# care.net
KiCad netlist of a schematic drawn in Altium Designer
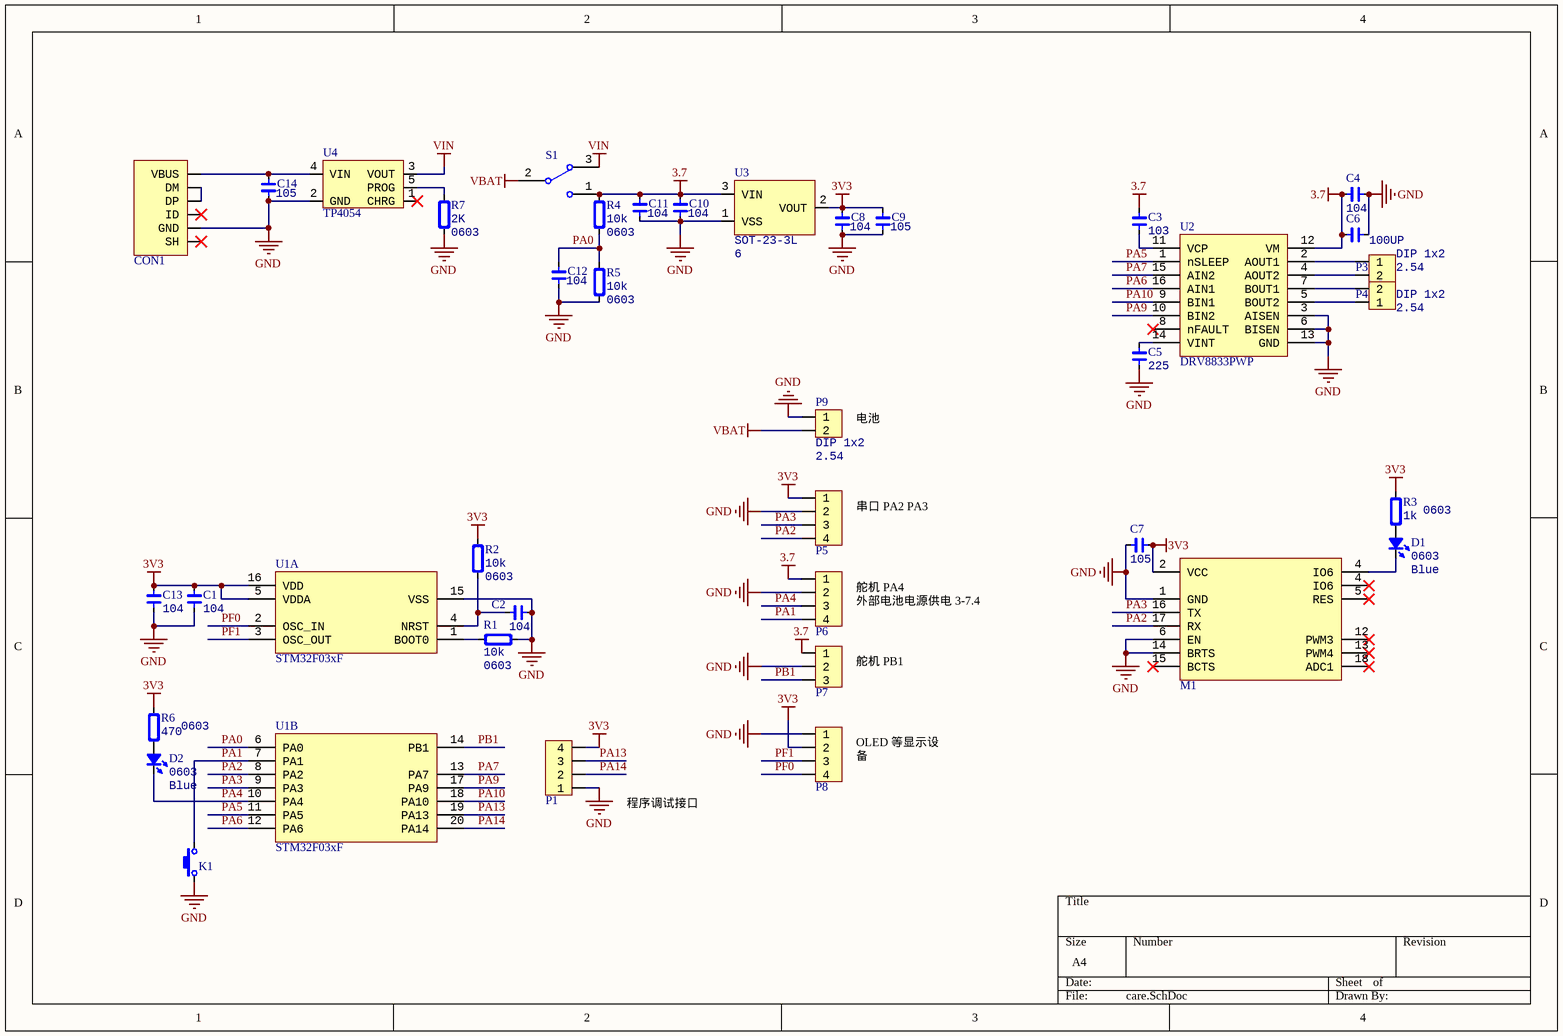
[diagram p0: care.SchDoc]

(export (version "E")
  (design (tool "Eeschema 10.0.6"))
  (components
    (comp (ref "C1")
      (value "104")
      (footprint "PCB_PassiveCap:CAP_0603")
      (description "Capacitor")
      (libsource (lib "") (part "Cap_0603_2"))
    )
    (comp (ref "C2")
      (value "104")
      (footprint "PCB_PassiveCap:CAP_0603")
      (description "Capacitor")
      (libsource (lib "SCH_Passive") (part "Cap_0603"))
    )
    (comp (ref "C3")
      (value "103")
      (footprint "PCB_PassiveCap:CAP_0603")
      (description "Capacitor")
      (libsource (lib "") (part "Cap_0603_2"))
    )
    (comp (ref "C4")
      (value "104")
      (footprint "PCB_PassiveCap:CAP_0603")
      (description "Capacitor")
      (libsource (lib "SCH_Passive") (part "Cap_0603"))
    )
    (comp (ref "C5")
      (value "225")
      (footprint "PCB_PassiveCap:CAP_0603")
      (description "Capacitor")
      (libsource (lib "") (part "Cap_0603_2"))
    )
    (comp (ref "C6")
      (value "100UP")
      (footprint "PCB_PassiveCap:CAP_TAN_B1210")
      (description "Capacitor")
      (libsource (lib "SCH_Passive") (part "Cap_0603"))
    )
    (comp (ref "C7")
      (value "105")
      (footprint "PCB_PassiveCap:CAP_0603")
      (description "Capacitor")
      (libsource (lib "") (part "Cap_0603_3"))
    )
    (comp (ref "C8")
      (value "104")
      (footprint "PCB_PassiveCap:CAP_0603")
      (description "Capacitor")
      (libsource (lib "") (part "Cap_0603_1"))
    )
    (comp (ref "C9")
      (value "105")
      (footprint "PCB_PassiveCap:CAP_0603")
      (description "Capacitor")
      (libsource (lib "") (part "Cap_0603_1"))
    )
    (comp (ref "C10")
      (value "104")
      (footprint "PCB_PassiveCap:CAP_0603")
      (description "Capacitor")
      (libsource (lib "") (part "Cap_0603_1"))
    )
    (comp (ref "C11")
      (value "104")
      (footprint "PCB_PassiveCap:CAP_0603")
      (description "Capacitor")
      (libsource (lib "") (part "Cap_0603_1"))
    )
    (comp (ref "C12")
      (value "104")
      (footprint "PCB_PassiveCap:CAP_0603")
      (description "Capacitor")
      (libsource (lib "") (part "Cap_0603_1"))
    )
    (comp (ref "C13")
      (value "104")
      (footprint "PCB_PassiveCap:CAP_0603")
      (description "Capacitor")
      (libsource (lib "") (part "Cap_0603_2"))
    )
    (comp (ref "C14")
      (value "105")
      (footprint "PCB_PassiveCap:CAP_0603")
      (description "Capacitor")
      (libsource (lib "") (part "Cap_0603_1"))
    )
    (comp (ref "CON1")
      (value "MicroUSB")
      (footprint "PCB_USB:USB_Micro-AB")
      (description "USB")
      (libsource (lib "SCH_USB") (part "USB_Micro"))
    )
    (comp (ref "D1")
      (value "Blue")
      (footprint "PCB_ActiveLED:LED_0603_RED")
      (description "LED")
      (fields (field (name "TYPE") "0603"))
      (libsource (lib "SCH_Active") (part "LED_0603"))
    )
    (comp (ref "D2")
      (value "Blue")
      (footprint "PCB_ActiveLED:LED_0603_RED")
      (description "LED")
      (fields (field (name "TYPE") "0603"))
      (libsource (lib "SCH_Active") (part "LED_0603"))
    )
    (comp (ref "K1")
      (value "ButtonTACT")
      (footprint "PCB_Switch:ButtonTACT_3x4x2_180H")
      (description "Button")
      (libsource (lib "SCH_Switch") (part "ButtonTACT_3x4x2_180"))
    )
    (comp (ref "M1")
      (value "RF-BM-S02")
      (footprint "PCB_Module:RF-BM-S02")
      (description "Module")
      (libsource (lib "SCH_Module") (part "RF-BM-S02"))
    )
    (comp (ref "P1")
      (value "HDR1x4_1.27")
      (footprint "PCB_ConnectorHDR:HDR1X4_2.54_180")
      (description "Header")
      (libsource (lib "SCH_ConnectorHDR") (part "HDR1x4_1.27"))
    )
    (comp (ref "P3")
      (value "2.54")
      (footprint "PCB_ConnectorHDR:HDR1X2_2.54_180")
      (description "Header")
      (fields (field (name "TYPE") "DIP 1x2") (field (name "Comment") "DIP 1x2"))
      (libsource (lib "") (part "HDR1x2_2.54_1"))
    )
    (comp (ref "P4")
      (value "2.54")
      (footprint "PCB_ConnectorHDR:HDR1X2_2.54_180")
      (description "Header")
      (fields (field (name "TYPE") "DIP 1x2") (field (name "Comment") "DIP 1x2"))
      (libsource (lib "SCH_ConnectorHDR") (part "HDR1x2_2.54"))
    )
    (comp (ref "P5")
      (value "HDR1x4_2.54")
      (footprint "PCB_ConnectorHDR:HDR1x4_2.54_180")
      (description "Header")
      (libsource (lib "SCH_ConnectorHDR") (part "HDR1x4_2.54"))
    )
    (comp (ref "P6")
      (value "HDR1x4_2.54")
      (footprint "PCB_ConnectorHDR:HDR1x4_2.54_180")
      (description "Header")
      (libsource (lib "SCH_ConnectorHDR") (part "HDR1x4_2.54"))
    )
    (comp (ref "P7")
      (value "HDR1x3_2.54")
      (footprint "PCB_ConnectorHDR:HDR1X3_2.54_180")
      (description "Header")
      (libsource (lib "SCH_ConnectorHDR") (part "HDR1x3_2.54"))
    )
    (comp (ref "P8")
      (value "HDR1x4_2.54")
      (footprint "PCB_ConnectorHDR:HDR1x4_2.54_180")
      (description "Header")
      (libsource (lib "SCH_ConnectorHDR") (part "HDR1x4_2.54"))
    )
    (comp (ref "P9")
      (value "2.54")
      (footprint "PCB_ConnectorHDR:HDR1X2_2.54_180")
      (description "Header")
      (fields (field (name "TYPE") "DIP 1x2") (field (name "Comment") "DIP 1x2"))
      (libsource (lib "") (part "HDR1x2_2.54_1"))
    )
    (comp (ref "R1")
      (value "10k")
      (footprint "PCB_PassiveRes:RES_0603")
      (description "Resistor")
      (fields (field (name "TYPE") "0603"))
      (libsource (lib "SCH_Passive") (part "Res_0603"))
    )
    (comp (ref "R2")
      (value "10k")
      (footprint "PCB_PassiveRes:RES_0603")
      (description "Resistor")
      (fields (field (name "TYPE") "0603"))
      (libsource (lib "SCH_Passive") (part "Res_0603"))
    )
    (comp (ref "R3")
      (value "1k")
      (footprint "PCB_PassiveRes:RES_0603")
      (description "Resistor")
      (fields (field (name "TYPE") "0603"))
      (libsource (lib "SCH_Passive") (part "Res_0603"))
    )
    (comp (ref "R4")
      (value "10k")
      (footprint "PCB_PassiveRes:RES_0603")
      (description "Resistor")
      (fields (field (name "TYPE") "0603"))
      (libsource (lib "SCH_Passive") (part "Res_0603"))
    )
    (comp (ref "R5")
      (value "10k")
      (footprint "PCB_PassiveRes:RES_0603")
      (description "Resistor")
      (fields (field (name "TYPE") "0603"))
      (libsource (lib "SCH_Passive") (part "Res_0603"))
    )
    (comp (ref "R6")
      (value "470")
      (footprint "PCB_PassiveRes:RES_0603")
      (description "Resistor")
      (fields (field (name "TYPE") "0603"))
      (libsource (lib "SCH_Passive") (part "Res_0603"))
    )
    (comp (ref "R7")
      (value "2K")
      (footprint "PCB_PassiveRes:RES_0603")
      (description "Resistor")
      (fields (field (name "TYPE") "0603"))
      (libsource (lib "SCH_Passive") (part "Res_0603"))
    )
    (comp (ref "S1")
      (value "SPDT 3P")
      (footprint "PCB_Switch:SwitchSPDT_2.8X6.6_90")
      (description "Switch")
      (libsource (lib "SCH_Switch") (part "SwitchSPDT_2.8x6.6_90"))
    )
    (comp (ref "U1")
      (value "STM32F03xF")
      (footprint "PCB_IntegratedCircuit:TSSOP_E170_P0.65_20")
      (description "MCU")
      (libsource (lib "SCH_IntegratedCircuit") (part "STM32F03xF"))
    )
    (comp (ref "U2")
      (value "DRV8833PWP")
      (footprint "PCB_IntegratedCircuit:TSSOP_E170_P0.65_16")
      (description "Touch")
      (libsource (lib "SCH_IntegratedCircuit") (part "DRV8833PWP"))
    )
    (comp (ref "U3")
      (value "6")
      (footprint "PCB_IntegratedCircuit:SOT23-3")
      (description "SOT-23-3L")
      (fields (field (name "TYPE") "SOT-23-3L"))
      (libsource (lib "SCH_Active") (part "ME6206A33M3G"))
    )
    (comp (ref "U4")
      (value "TP4054")
      (footprint "PCB_IntegratedCircuit:SOT23-5")
      (description "Power")
      (libsource (lib "SCH_IntegratedCircuit") (part "TP4054"))
    )
  )
  (nets
    (net (code "1") (name "/PA0") (class "Default")
      (node (ref "C12") (pin "2") (pinfunction "2_2") (pintype "passive"))
      (node (ref "R4") (pin "2") (pinfunction "2_2") (pintype "passive"))
      (node (ref "R5") (pin "1") (pinfunction "1_1") (pintype "passive"))
      (node (ref "U1") (pin "6") (pinfunction "PA0_6") (pintype "passive"))
    )
    (net (code "2") (name "/PA1") (class "Default")
      (node (ref "K1") (pin "2") (pinfunction "2_2") (pintype "passive"))
      (node (ref "P6") (pin "4") (pinfunction "4_4") (pintype "passive"))
      (node (ref "U1") (pin "7") (pinfunction "PA1_7") (pintype "passive"))
    )
    (net (code "3") (name "/PA2") (class "Default")
      (node (ref "M1") (pin "17") (pinfunction "RX_17") (pintype "passive"))
      (node (ref "P5") (pin "4") (pinfunction "4_4") (pintype "passive"))
      (node (ref "U1") (pin "8") (pinfunction "PA2_8") (pintype "passive"))
    )
    (net (code "4") (name "/PA3") (class "Default")
      (node (ref "M1") (pin "16") (pinfunction "TX_16") (pintype "passive"))
      (node (ref "P5") (pin "3") (pinfunction "3_3") (pintype "passive"))
      (node (ref "U1") (pin "9") (pinfunction "PA3_9") (pintype "passive"))
    )
    (net (code "5") (name "/PA4") (class "Default")
      (node (ref "D2") (pin "2") (pinfunction "K_2") (pintype "passive"))
      (node (ref "P6") (pin "3") (pinfunction "3_3") (pintype "passive"))
      (node (ref "U1") (pin "10") (pinfunction "PA4_10") (pintype "passive"))
    )
    (net (code "6") (name "/PA5") (class "Default")
      (node (ref "U1") (pin "11") (pinfunction "PA5_11") (pintype "passive"))
      (node (ref "U2") (pin "1") (pinfunction "nSLEEP_1") (pintype "passive"))
    )
    (net (code "7") (name "/PA6") (class "Default")
      (node (ref "U1") (pin "12") (pinfunction "PA6_12") (pintype "passive"))
      (node (ref "U2") (pin "16") (pinfunction "AIN1_16") (pintype "passive"))
    )
    (net (code "8") (name "/PA7") (class "Default")
      (node (ref "U1") (pin "13") (pinfunction "PA7_13") (pintype "passive"))
      (node (ref "U2") (pin "15") (pinfunction "AIN2_15") (pintype "passive"))
    )
    (net (code "9") (name "/PA9") (class "Default")
      (node (ref "U1") (pin "17") (pinfunction "PA9_17") (pintype "passive"))
      (node (ref "U2") (pin "10") (pinfunction "BIN2_10") (pintype "passive"))
    )
    (net (code "10") (name "/PA10") (class "Default")
      (node (ref "U1") (pin "18") (pinfunction "PA10_18") (pintype "passive"))
      (node (ref "U2") (pin "9") (pinfunction "BIN1_9") (pintype "passive"))
    )
    (net (code "11") (name "/PA13") (class "Default")
      (node (ref "P1") (pin "3") (pinfunction "3_3") (pintype "passive"))
      (node (ref "U1") (pin "19") (pinfunction "PA13_19") (pintype "passive"))
    )
    (net (code "12") (name "/PA14") (class "Default")
      (node (ref "P1") (pin "2") (pinfunction "2_2") (pintype "passive"))
      (node (ref "U1") (pin "20") (pinfunction "PA14_20") (pintype "passive"))
    )
    (net (code "13") (name "/PB1") (class "Default")
      (node (ref "P7") (pin "3") (pinfunction "3_3") (pintype "passive"))
      (node (ref "U1") (pin "14") (pinfunction "PB1_14") (pintype "passive"))
    )
    (net (code "14") (name "/PF0") (class "Default")
      (node (ref "P8") (pin "4") (pinfunction "4_4") (pintype "passive"))
      (node (ref "U1") (pin "2") (pinfunction "OSC_IN_2") (pintype "passive"))
    )
    (net (code "15") (name "/PF1") (class "Default")
      (node (ref "P8") (pin "3") (pinfunction "3_3") (pintype "passive"))
      (node (ref "U1") (pin "3") (pinfunction "OSC_OUT_3") (pintype "passive"))
    )
    (net (code "16") (name "3.7") (class "Default")
      (node (ref "C10") (pin "2") (pinfunction "2_2") (pintype "passive"))
      (node (ref "C11") (pin "2") (pinfunction "2_2") (pintype "passive"))
      (node (ref "C3") (pin "1") (pinfunction "1_1") (pintype "passive"))
      (node (ref "C4") (pin "1") (pinfunction "1_1") (pintype "passive"))
      (node (ref "C6") (pin "1") (pinfunction "1_1") (pintype "passive"))
      (node (ref "P6") (pin "1") (pinfunction "1_1") (pintype "passive"))
      (node (ref "P7") (pin "1") (pinfunction "1_1") (pintype "passive"))
      (node (ref "R4") (pin "1") (pinfunction "1_1") (pintype "passive"))
      (node (ref "S1") (pin "1") (pinfunction "1_1") (pintype "passive"))
      (node (ref "U2") (pin "12") (pinfunction "VM_12") (pintype "passive"))
      (node (ref "U3") (pin "3") (pinfunction "VIN_3") (pintype "passive"))
    )
    (net (code "17") (name "3V3") (class "Default")
      (node (ref "C1") (pin "1") (pinfunction "1_1") (pintype "passive"))
      (node (ref "C13") (pin "1") (pinfunction "1_1") (pintype "passive"))
      (node (ref "C7") (pin "1") (pinfunction "1_1") (pintype "passive"))
      (node (ref "C8") (pin "2") (pinfunction "2_2") (pintype "passive"))
      (node (ref "C9") (pin "2") (pinfunction "2_2") (pintype "passive"))
      (node (ref "M1") (pin "2") (pinfunction "VCC_2") (pintype "passive"))
      (node (ref "P1") (pin "4") (pinfunction "4_4") (pintype "passive"))
      (node (ref "P5") (pin "1") (pinfunction "1_1") (pintype "passive"))
      (node (ref "P8") (pin "2") (pinfunction "2_2") (pintype "passive"))
      (node (ref "R2") (pin "1") (pinfunction "1_1") (pintype "passive"))
      (node (ref "R3") (pin "1") (pinfunction "1_1") (pintype "passive"))
      (node (ref "R6") (pin "1") (pinfunction "1_1") (pintype "passive"))
      (node (ref "U1") (pin "16") (pinfunction "VDD_16") (pintype "passive"))
      (node (ref "U1") (pin "5") (pinfunction "VDDA_5") (pintype "passive"))
      (node (ref "U3") (pin "2") (pinfunction "VOUT_2") (pintype "passive"))
    )
    (net (code "18") (name "GND") (class "Default")
      (node (ref "C1") (pin "2") (pinfunction "2_2") (pintype "passive"))
      (node (ref "C10") (pin "1") (pinfunction "1_1") (pintype "passive"))
      (node (ref "C11") (pin "1") (pinfunction "1_1") (pintype "passive"))
      (node (ref "C12") (pin "1") (pinfunction "1_1") (pintype "passive"))
      (node (ref "C13") (pin "2") (pinfunction "2_2") (pintype "passive"))
      (node (ref "C14") (pin "1") (pinfunction "1_1") (pintype "passive"))
      (node (ref "C2") (pin "2") (pinfunction "2_2") (pintype "passive"))
      (node (ref "C4") (pin "2") (pinfunction "2_2") (pintype "passive"))
      (node (ref "C5") (pin "2") (pinfunction "2_2") (pintype "passive"))
      (node (ref "C6") (pin "2") (pinfunction "2_2") (pintype "passive"))
      (node (ref "C7") (pin "2") (pinfunction "2_2") (pintype "passive"))
      (node (ref "C8") (pin "1") (pinfunction "1_1") (pintype "passive"))
      (node (ref "C9") (pin "1") (pinfunction "1_1") (pintype "passive"))
      (node (ref "CON1") (pin "5") (pinfunction "GND_5") (pintype "passive"))
      (node (ref "K1") (pin "1") (pinfunction "1_1") (pintype "passive"))
      (node (ref "M1") (pin "1") (pinfunction "GND_1") (pintype "passive"))
      (node (ref "M1") (pin "14") (pinfunction "BRTS_14") (pintype "passive"))
      (node (ref "M1") (pin "6") (pinfunction "EN_6") (pintype "passive"))
      (node (ref "P1") (pin "1") (pinfunction "1_1") (pintype "passive"))
      (node (ref "P5") (pin "2") (pinfunction "2_2") (pintype "passive"))
      (node (ref "P6") (pin "2") (pinfunction "2_2") (pintype "passive"))
      (node (ref "P7") (pin "2") (pinfunction "2_2") (pintype "passive"))
      (node (ref "P8") (pin "1") (pinfunction "1_1") (pintype "passive"))
      (node (ref "P9") (pin "1") (pinfunction "1_1") (pintype "passive"))
      (node (ref "R1") (pin "2") (pinfunction "2_2") (pintype "passive"))
      (node (ref "R5") (pin "2") (pinfunction "2_2") (pintype "passive"))
      (node (ref "R7") (pin "2") (pinfunction "2_2") (pintype "passive"))
      (node (ref "U1") (pin "15") (pinfunction "VSS_15") (pintype "passive"))
      (node (ref "U2") (pin "13") (pinfunction "GND_13") (pintype "passive"))
      (node (ref "U2") (pin "3") (pinfunction "AISEN_3") (pintype "passive"))
      (node (ref "U2") (pin "6") (pinfunction "BISEN_6") (pintype "passive"))
      (node (ref "U3") (pin "1") (pinfunction "VSS_1") (pintype "passive"))
      (node (ref "U4") (pin "2") (pinfunction "GND_2") (pintype "passive"))
    )
    (net (code "19") (name "Net-(CON1-DM)") (class "Default")
      (node (ref "CON1") (pin "2") (pinfunction "DM_2") (pintype "passive"))
      (node (ref "CON1") (pin "3") (pinfunction "DP_3") (pintype "passive"))
    )
    (net (code "20") (name "Net-(CON1-VBUS)") (class "Default")
      (node (ref "C14") (pin "2") (pinfunction "2_2") (pintype "passive"))
      (node (ref "CON1") (pin "1") (pinfunction "VBUS_1") (pintype "passive"))
      (node (ref "U4") (pin "4") (pinfunction "VIN_4") (pintype "passive"))
    )
    (net (code "21") (name "Net-(D1-A)") (class "Default")
      (node (ref "D1") (pin "1") (pinfunction "A_1") (pintype "passive"))
      (node (ref "R3") (pin "2") (pinfunction "2_2") (pintype "passive"))
    )
    (net (code "22") (name "Net-(D1-K)") (class "Default")
      (node (ref "D1") (pin "2") (pinfunction "K_2") (pintype "passive"))
      (node (ref "M1") (pin "4") (pinfunction "IO6_4") (pintype "passive"))
    )
    (net (code "23") (name "Net-(D2-A)") (class "Default")
      (node (ref "D2") (pin "1") (pinfunction "A_1") (pintype "passive"))
      (node (ref "R6") (pin "2") (pinfunction "2_2") (pintype "passive"))
    )
    (net (code "24") (name "Net-(U1A-BOOT0)") (class "Default")
      (node (ref "R1") (pin "1") (pinfunction "1_1") (pintype "passive"))
      (node (ref "U1") (pin "1") (pinfunction "BOOT0_1") (pintype "passive"))
    )
    (net (code "25") (name "Net-(U1A-NRST)") (class "Default")
      (node (ref "C2") (pin "1") (pinfunction "1_1") (pintype "passive"))
      (node (ref "R2") (pin "2") (pinfunction "2_2") (pintype "passive"))
      (node (ref "U1") (pin "4") (pinfunction "NRST_4") (pintype "passive"))
    )
    (net (code "26") (name "Net-(U2-AOUT1)") (class "Default")
      (node (ref "P3") (pin "1") (pinfunction "1_1") (pintype "passive"))
      (node (ref "U2") (pin "2") (pinfunction "AOUT1_2") (pintype "passive"))
    )
    (net (code "27") (name "Net-(U2-AOUT2)") (class "Default")
      (node (ref "P3") (pin "2") (pinfunction "2_2") (pintype "passive"))
      (node (ref "U2") (pin "4") (pinfunction "AOUT2_4") (pintype "passive"))
    )
    (net (code "28") (name "Net-(U2-BOUT1)") (class "Default")
      (node (ref "P4") (pin "2") (pinfunction "2_2") (pintype "passive"))
      (node (ref "U2") (pin "7") (pinfunction "BOUT1_7") (pintype "passive"))
    )
    (net (code "29") (name "Net-(U2-BOUT2)") (class "Default")
      (node (ref "P4") (pin "1") (pinfunction "1_1") (pintype "passive"))
      (node (ref "U2") (pin "5") (pinfunction "BOUT2_5") (pintype "passive"))
    )
    (net (code "30") (name "Net-(U2-VCP)") (class "Default")
      (node (ref "C3") (pin "2") (pinfunction "2_2") (pintype "passive"))
      (node (ref "U2") (pin "11") (pinfunction "VCP_11") (pintype "passive"))
    )
    (net (code "31") (name "Net-(U2-VINT)") (class "Default")
      (node (ref "C5") (pin "1") (pinfunction "1_1") (pintype "passive"))
      (node (ref "U2") (pin "14") (pinfunction "VINT_14") (pintype "passive"))
    )
    (net (code "32") (name "Net-(U4-PROG)") (class "Default")
      (node (ref "R7") (pin "1") (pinfunction "1_1") (pintype "passive"))
      (node (ref "U4") (pin "5") (pinfunction "PROG_5") (pintype "passive"))
    )
    (net (code "33") (name "VBAT") (class "Default")
      (node (ref "P9") (pin "2") (pinfunction "2_2") (pintype "passive"))
      (node (ref "S1") (pin "2") (pinfunction "2_2") (pintype "passive"))
    )
    (net (code "34") (name "VIN") (class "Default")
      (node (ref "S1") (pin "3") (pinfunction "3_3") (pintype "passive"))
      (node (ref "U4") (pin "3") (pinfunction "VOUT_3") (pintype "passive"))
    )
    (net (code "35") (name "unconnected-(CON1-ID-Pad4)") (class "Default")
      (node (ref "CON1") (pin "4") (pinfunction "ID_4") (pintype "passive+no_connect"))
    )
    (net (code "36") (name "unconnected-(CON1-SH-Pad0)") (class "Default")
      (node (ref "CON1") (pin "0") (pinfunction "SH_0") (pintype "passive+no_connect"))
    )
    (net (code "37") (name "unconnected-(M1-ADC1-Pad18)") (class "Default")
      (node (ref "M1") (pin "18") (pinfunction "ADC1_18") (pintype "passive+no_connect"))
    )
    (net (code "38") (name "unconnected-(M1-BCTS-Pad15)") (class "Default")
      (node (ref "M1") (pin "15") (pinfunction "BCTS_15") (pintype "passive+no_connect"))
    )
    (net (code "39") (name "unconnected-(M1-IO6-Pad4)") (class "Default")
      (node (ref "M1") (pin "4") (pinfunction "IO6_4") (pintype "passive+no_connect"))
    )
    (net (code "40") (name "unconnected-(M1-PWM3-Pad12)") (class "Default")
      (node (ref "M1") (pin "12") (pinfunction "PWM3_12") (pintype "passive+no_connect"))
    )
    (net (code "41") (name "unconnected-(M1-PWM4-Pad13)") (class "Default")
      (node (ref "M1") (pin "13") (pinfunction "PWM4_13") (pintype "passive+no_connect"))
    )
    (net (code "42") (name "unconnected-(M1-RES-Pad5)") (class "Default")
      (node (ref "M1") (pin "5") (pinfunction "RES_5") (pintype "passive+no_connect"))
    )
    (net (code "43") (name "unconnected-(U2-nFAULT-Pad8)") (class "Default")
      (node (ref "U2") (pin "8") (pinfunction "nFAULT_8") (pintype "passive+no_connect"))
    )
    (net (code "44") (name "unconnected-(U4-CHRG-Pad1)") (class "Default")
      (node (ref "U4") (pin "1") (pinfunction "CHRG_1") (pintype "passive+no_connect"))
    )
  )
)
